# MCU103A_F280039C_Device.net
KiCad netlist of a schematic drawn in Altium Designer
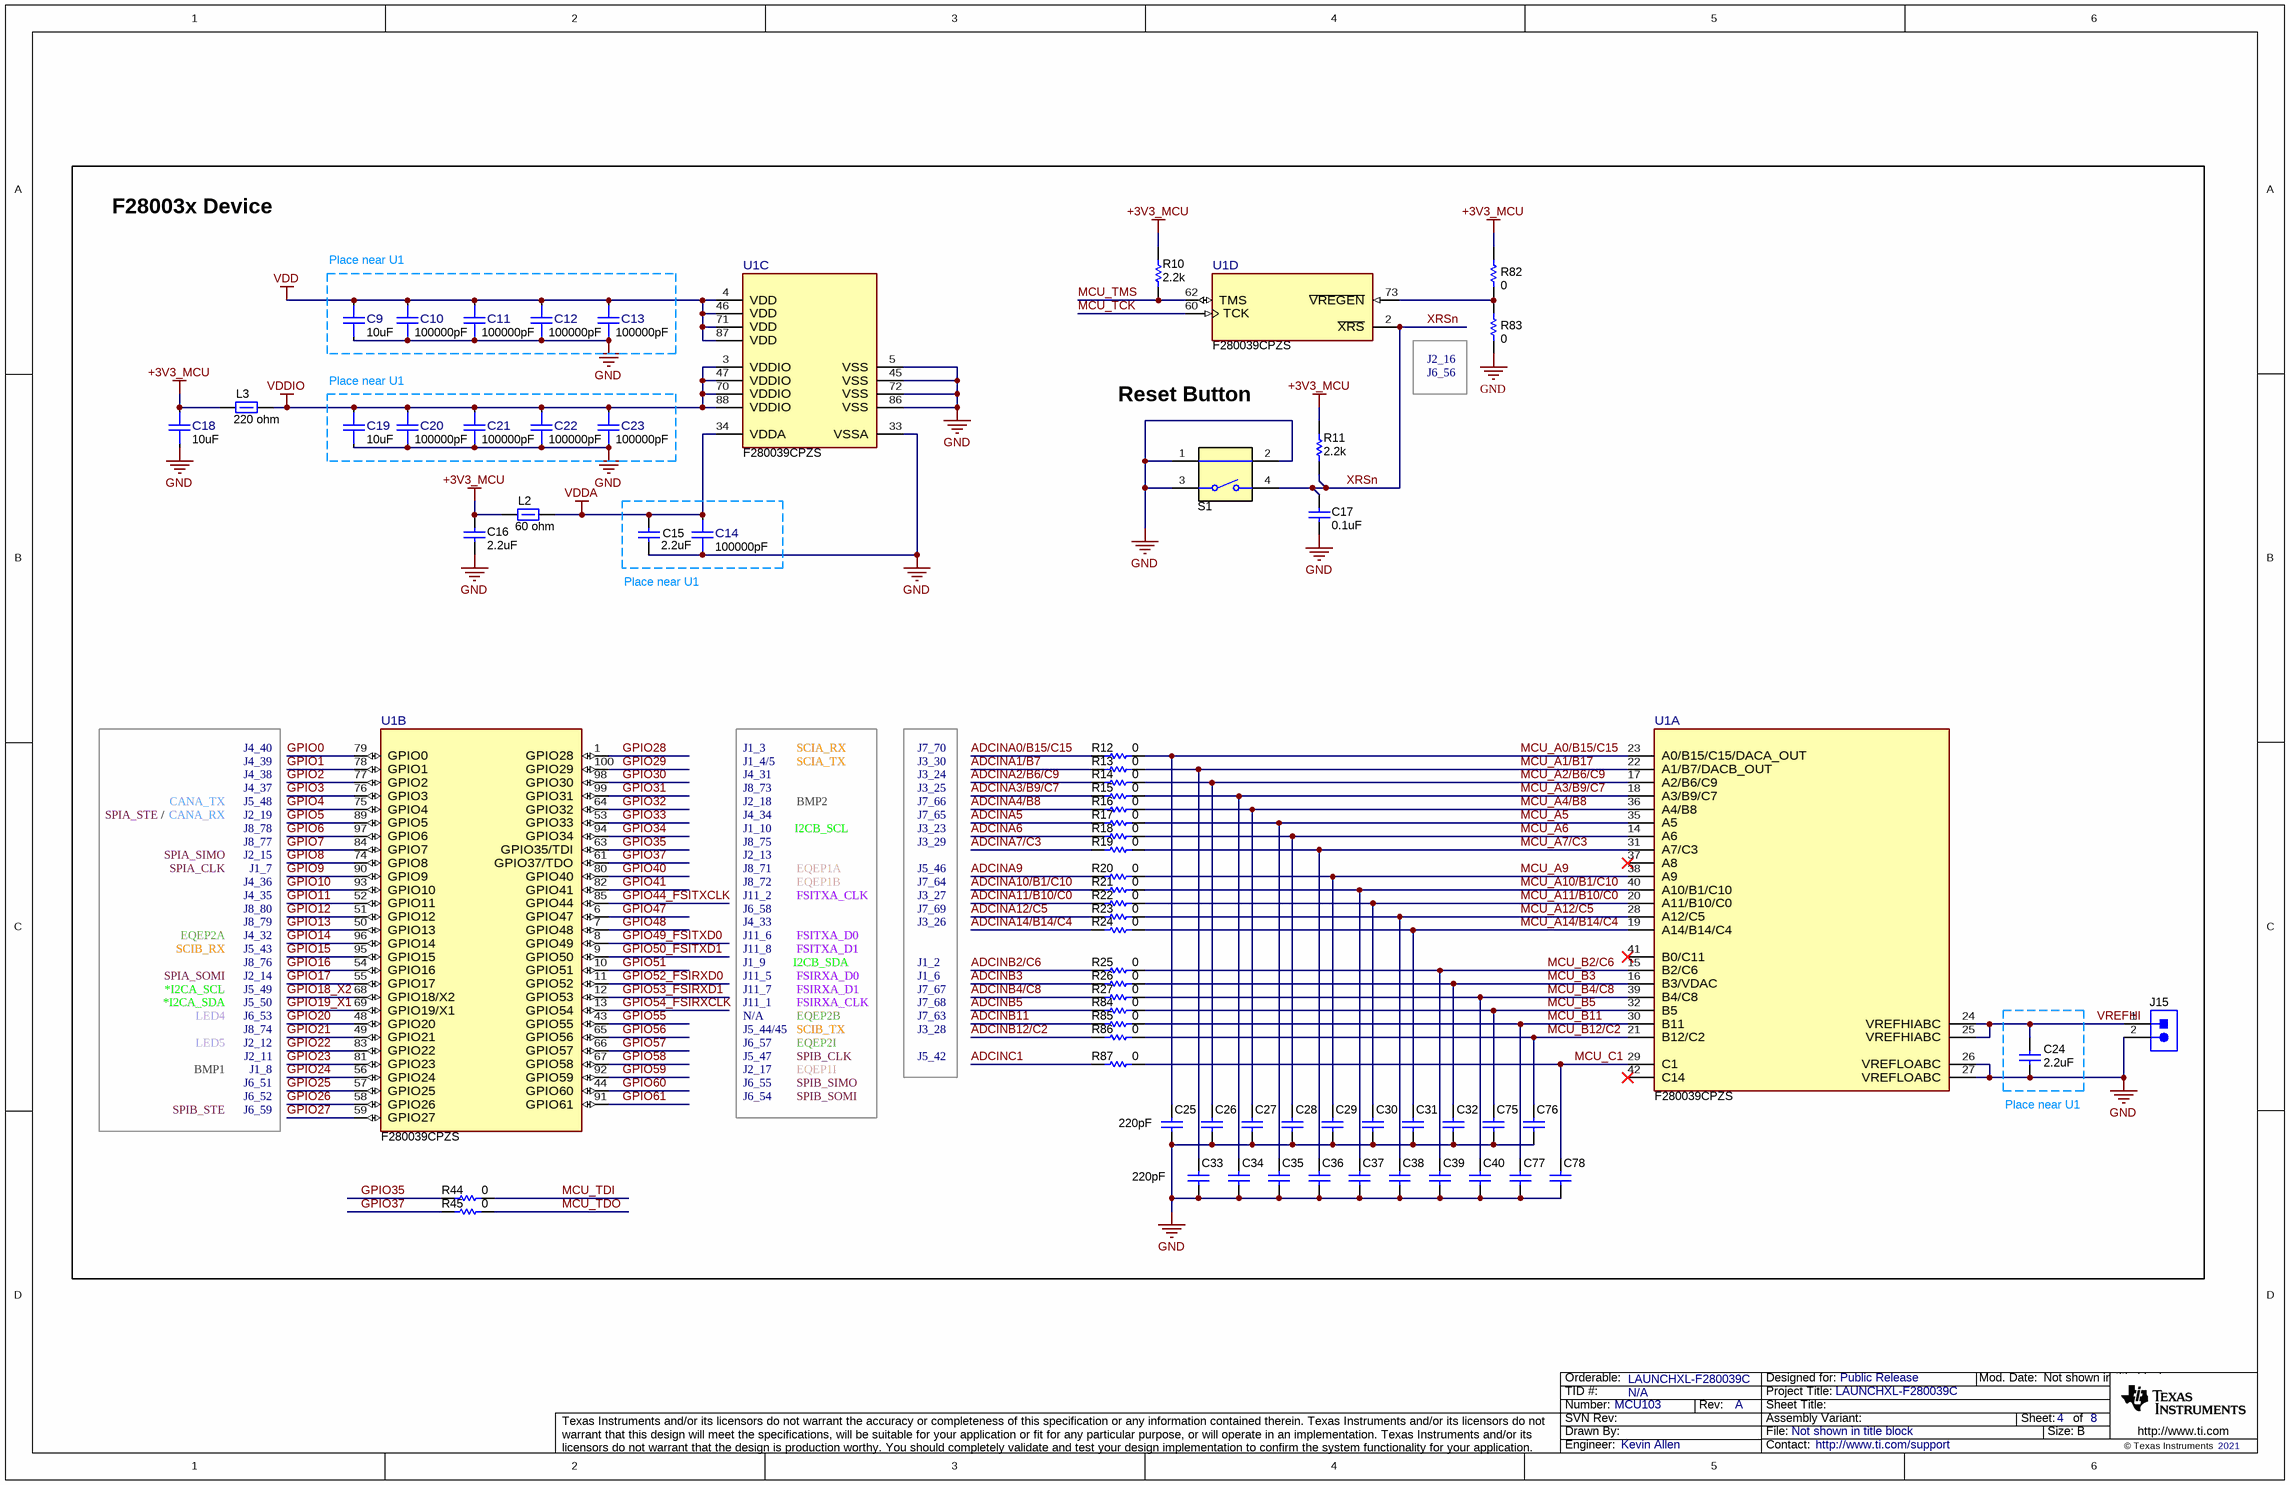
[diagram p0: MCU103A_F280039C_Device.SchDoc]

(export (version "E")
  (design (tool "Eeschema 10.0.6"))
  (components
    (comp (ref "C9")
      (value "CC0603KRX5R6BB106")
      (footprint "FP-CC0603KRX5R6BB106_0603-MFG")
      (description "Cap Ceramic 10uF 10V X5R 10% SMD 0603 85C Paper T/R")
      (fields
        (field (name "DIGIKEY PART NUMBER") "311-1782-1-ND")
        (field (name "MANUFACTURER") "YAGEO")
        (field (name "VALUEDISPLAYED") "10uF")
      )
      (libsource (lib "Altium Vault - TI") (part "SYM-CC0603KRX5R6BB106"))
    )
    (comp (ref "C10")
      (value "885012205018")
      (footprint "FP-885012205018_0402-MFG")
      (description "0.1µF ±10% 10V Ceramic Capacitor X7R 0402 (1005 Metric)")
      (fields
        (field (name "MANUFACTURER") "Wurth Electronics")
        (field (name "MOUSER PART NUMBER") "710-885012205018")
        (field (name "VALUEDISPLAYED") "100000pF")
      )
      (libsource (lib "Altium Vault - TI") (part "SYM-885012205018"))
    )
    (comp (ref "C11")
      (value "885012205018")
      (footprint "FP-885012205018_0402-MFG")
      (description "0.1µF ±10% 10V Ceramic Capacitor X7R 0402 (1005 Metric)")
      (fields
        (field (name "MANUFACTURER") "Wurth Electronics")
        (field (name "MOUSER PART NUMBER") "710-885012205018")
        (field (name "VALUEDISPLAYED") "100000pF")
      )
      (libsource (lib "Altium Vault - TI") (part "SYM-885012205018"))
    )
    (comp (ref "C12")
      (value "885012205018")
      (footprint "FP-885012205018_0402-MFG")
      (description "0.1µF ±10% 10V Ceramic Capacitor X7R 0402 (1005 Metric)")
      (fields
        (field (name "MANUFACTURER") "Wurth Electronics")
        (field (name "MOUSER PART NUMBER") "710-885012205018")
        (field (name "VALUEDISPLAYED") "100000pF")
      )
      (libsource (lib "Altium Vault - TI") (part "SYM-885012205018"))
    )
    (comp (ref "C13")
      (value "885012205018")
      (footprint "FP-885012205018_0402-MFG")
      (description "0.1µF ±10% 10V Ceramic Capacitor X7R 0402 (1005 Metric)")
      (fields
        (field (name "MANUFACTURER") "Wurth Electronics")
        (field (name "MOUSER PART NUMBER") "710-885012205018")
        (field (name "VALUEDISPLAYED") "100000pF")
      )
      (libsource (lib "Altium Vault - TI") (part "SYM-885012205018"))
    )
    (comp (ref "C14")
      (value "885012205018")
      (footprint "FP-885012205018_0402-MFG")
      (description "0.1µF ±10% 10V Ceramic Capacitor X7R 0402 (1005 Metric)")
      (fields
        (field (name "MANUFACTURER") "Wurth Electronics")
        (field (name "MOUSER PART NUMBER") "710-885012205018")
        (field (name "VALUEDISPLAYED") "100000pF")
      )
      (libsource (lib "Altium Vault - TI") (part "SYM-885012205018"))
    )
    (comp (ref "C15")
      (value "GRM188R61A225KE34D")
      (footprint "0603")
      (description "CAP, CERM, 2.2 uF, 10 V, +/- 10%, X5R, 0603")
      (fields
        (field (name "VALUEDISPLAYED") "2.2uF")
        (field (name "MANUFACTURER") "MuRata")
        (field (name "PUBLISHER") "Texas Instruments")
      )
      (libsource (lib "Altium Vault - TI") (part "Capacitor"))
    )
    (comp (ref "C16")
      (value "GRM188R61A225KE34D")
      (footprint "0603")
      (description "CAP, CERM, 2.2 uF, 10 V, +/- 10%, X5R, 0603")
      (fields
        (field (name "VALUEDISPLAYED") "2.2uF")
        (field (name "MANUFACTURER") "MuRata")
        (field (name "PUBLISHER") "Texas Instruments")
      )
      (libsource (lib "Altium Vault - TI") (part "Capacitor"))
    )
    (comp (ref "C17")
      (value "GRM155R71A104KA01D")
      (footprint "0402")
      (description "CAP, CERM, 0.1 uF, 10 V, +/- 10%, X7R, 0402")
      (fields
        (field (name "VALUEDISPLAYED") "0.1uF")
        (field (name "MANUFACTURER") "MuRata")
        (field (name "PUBLISHER") "Texas Instruments")
      )
      (libsource (lib "Altium Vault - TI") (part "Capacitor"))
    )
    (comp (ref "C18")
      (value "CC0603KRX5R6BB106")
      (footprint "FP-CC0603KRX5R6BB106_0603-MFG")
      (description "Cap Ceramic 10uF 10V X5R 10% SMD 0603 85C Paper T/R")
      (fields
        (field (name "DIGIKEY PART NUMBER") "311-1782-1-ND")
        (field (name "MANUFACTURER") "YAGEO")
        (field (name "VALUEDISPLAYED") "10uF")
      )
      (libsource (lib "Altium Vault - TI") (part "SYM-CC0603KRX5R6BB106"))
    )
    (comp (ref "C19")
      (value "CC0603KRX5R6BB106")
      (footprint "FP-CC0603KRX5R6BB106_0603-MFG")
      (description "Cap Ceramic 10uF 10V X5R 10% SMD 0603 85C Paper T/R")
      (fields
        (field (name "DIGIKEY PART NUMBER") "311-1782-1-ND")
        (field (name "MANUFACTURER") "YAGEO")
        (field (name "VALUEDISPLAYED") "10uF")
      )
      (libsource (lib "Altium Vault - TI") (part "SYM-CC0603KRX5R6BB106"))
    )
    (comp (ref "C20")
      (value "885012205018")
      (footprint "FP-885012205018_0402-MFG")
      (description "0.1µF ±10% 10V Ceramic Capacitor X7R 0402 (1005 Metric)")
      (fields
        (field (name "MANUFACTURER") "Wurth Electronics")
        (field (name "MOUSER PART NUMBER") "710-885012205018")
        (field (name "VALUEDISPLAYED") "100000pF")
      )
      (libsource (lib "Altium Vault - TI") (part "SYM-885012205018"))
    )
    (comp (ref "C21")
      (value "885012205018")
      (footprint "FP-885012205018_0402-MFG")
      (description "0.1µF ±10% 10V Ceramic Capacitor X7R 0402 (1005 Metric)")
      (fields
        (field (name "MANUFACTURER") "Wurth Electronics")
        (field (name "MOUSER PART NUMBER") "710-885012205018")
        (field (name "VALUEDISPLAYED") "100000pF")
      )
      (libsource (lib "Altium Vault - TI") (part "SYM-885012205018"))
    )
    (comp (ref "C22")
      (value "885012205018")
      (footprint "FP-885012205018_0402-MFG")
      (description "0.1µF ±10% 10V Ceramic Capacitor X7R 0402 (1005 Metric)")
      (fields
        (field (name "MANUFACTURER") "Wurth Electronics")
        (field (name "MOUSER PART NUMBER") "710-885012205018")
        (field (name "VALUEDISPLAYED") "100000pF")
      )
      (libsource (lib "Altium Vault - TI") (part "SYM-885012205018"))
    )
    (comp (ref "C23")
      (value "885012205018")
      (footprint "FP-885012205018_0402-MFG")
      (description "0.1µF ±10% 10V Ceramic Capacitor X7R 0402 (1005 Metric)")
      (fields
        (field (name "MANUFACTURER") "Wurth Electronics")
        (field (name "MOUSER PART NUMBER") "710-885012205018")
        (field (name "VALUEDISPLAYED") "100000pF")
      )
      (libsource (lib "Altium Vault - TI") (part "SYM-885012205018"))
    )
    (comp (ref "C24")
      (value "GRM188R61A225KE34D")
      (footprint "0603")
      (description "CAP, CERM, 2.2 uF, 10 V, +/- 10%, X5R, 0603")
      (fields
        (field (name "MANUFACTURER") "MuRata")
        (field (name "VALUEDISPLAYED") "2.2uF")
        (field (name "PUBLISHER") "Texas Instruments")
      )
      (libsource (lib "Altium Vault - TI") (part "Capacitor"))
    )
    (comp (ref "C25")
      (value "885012005063")
      (footprint "0402")
      (description "CAP, CERM, 220 pF, 50 V, +/- 5%, C0G/NP0, 0402")
      (fields
        (field (name "MANUFACTURER") "Wurth Elektronik")
        (field (name "VALUEDISPLAYED") "220pF")
        (field (name "PUBLISHER") "Texas Instruments")
      )
      (libsource (lib "Altium Vault - TI") (part "Capacitor"))
    )
    (comp (ref "C26")
      (value "885012005063")
      (footprint "0402")
      (description "CAP, CERM, 220 pF, 50 V, +/- 5%, C0G/NP0, 0402")
      (fields (field (name "MANUFACTURER") "Wurth Elektronik") (field (name "PUBLISHER") "Texas Instruments"))
      (libsource (lib "Altium Vault - TI") (part "Capacitor"))
    )
    (comp (ref "C27")
      (value "885012005063")
      (footprint "0402")
      (description "CAP, CERM, 220 pF, 50 V, +/- 5%, C0G/NP0, 0402")
      (fields (field (name "MANUFACTURER") "Wurth Elektronik") (field (name "PUBLISHER") "Texas Instruments"))
      (libsource (lib "Altium Vault - TI") (part "Capacitor"))
    )
    (comp (ref "C28")
      (value "885012005063")
      (footprint "0402")
      (description "CAP, CERM, 220 pF, 50 V, +/- 5%, C0G/NP0, 0402")
      (fields (field (name "MANUFACTURER") "Wurth Elektronik") (field (name "PUBLISHER") "Texas Instruments"))
      (libsource (lib "Altium Vault - TI") (part "Capacitor"))
    )
    (comp (ref "C29")
      (value "885012005063")
      (footprint "0402")
      (description "CAP, CERM, 220 pF, 50 V, +/- 5%, C0G/NP0, 0402")
      (fields (field (name "MANUFACTURER") "Wurth Elektronik") (field (name "PUBLISHER") "Texas Instruments"))
      (libsource (lib "Altium Vault - TI") (part "Capacitor"))
    )
    (comp (ref "C30")
      (value "885012005063")
      (footprint "0402")
      (description "CAP, CERM, 220 pF, 50 V, +/- 5%, C0G/NP0, 0402")
      (fields (field (name "MANUFACTURER") "Wurth Elektronik") (field (name "PUBLISHER") "Texas Instruments"))
      (libsource (lib "Altium Vault - TI") (part "Capacitor"))
    )
    (comp (ref "C31")
      (value "885012005063")
      (footprint "0402")
      (description "CAP, CERM, 220 pF, 50 V, +/- 5%, C0G/NP0, 0402")
      (fields (field (name "MANUFACTURER") "Wurth Elektronik") (field (name "PUBLISHER") "Texas Instruments"))
      (libsource (lib "Altium Vault - TI") (part "Capacitor"))
    )
    (comp (ref "C32")
      (value "885012005063")
      (footprint "0402")
      (description "CAP, CERM, 220 pF, 50 V, +/- 5%, C0G/NP0, 0402")
      (fields (field (name "MANUFACTURER") "Wurth Elektronik") (field (name "PUBLISHER") "Texas Instruments"))
      (libsource (lib "Altium Vault - TI") (part "Capacitor"))
    )
    (comp (ref "C33")
      (value "885012005063")
      (footprint "0402")
      (description "CAP, CERM, 220 pF, 50 V, +/- 5%, C0G/NP0, 0402")
      (fields
        (field (name "MANUFACTURER") "Wurth Elektronik")
        (field (name "VALUEDISPLAYED") "220pF")
        (field (name "PUBLISHER") "Texas Instruments")
      )
      (libsource (lib "Altium Vault - TI") (part "Capacitor"))
    )
    (comp (ref "C34")
      (value "885012005063")
      (footprint "0402")
      (description "CAP, CERM, 220 pF, 50 V, +/- 5%, C0G/NP0, 0402")
      (fields (field (name "MANUFACTURER") "Wurth Elektronik") (field (name "PUBLISHER") "Texas Instruments"))
      (libsource (lib "Altium Vault - TI") (part "Capacitor"))
    )
    (comp (ref "C35")
      (value "885012005063")
      (footprint "0402")
      (description "CAP, CERM, 220 pF, 50 V, +/- 5%, C0G/NP0, 0402")
      (fields (field (name "MANUFACTURER") "Wurth Elektronik") (field (name "PUBLISHER") "Texas Instruments"))
      (libsource (lib "Altium Vault - TI") (part "Capacitor"))
    )
    (comp (ref "C36")
      (value "885012005063")
      (footprint "0402")
      (description "CAP, CERM, 220 pF, 50 V, +/- 5%, C0G/NP0, 0402")
      (fields (field (name "MANUFACTURER") "Wurth Elektronik") (field (name "PUBLISHER") "Texas Instruments"))
      (libsource (lib "Altium Vault - TI") (part "Capacitor"))
    )
    (comp (ref "C37")
      (value "885012005063")
      (footprint "0402")
      (description "CAP, CERM, 220 pF, 50 V, +/- 5%, C0G/NP0, 0402")
      (fields (field (name "MANUFACTURER") "Wurth Elektronik") (field (name "PUBLISHER") "Texas Instruments"))
      (libsource (lib "Altium Vault - TI") (part "Capacitor"))
    )
    (comp (ref "C38")
      (value "885012005063")
      (footprint "0402")
      (description "CAP, CERM, 220 pF, 50 V, +/- 5%, C0G/NP0, 0402")
      (fields (field (name "MANUFACTURER") "Wurth Elektronik") (field (name "PUBLISHER") "Texas Instruments"))
      (libsource (lib "Altium Vault - TI") (part "Capacitor"))
    )
    (comp (ref "C39")
      (value "885012005063")
      (footprint "0402")
      (description "CAP, CERM, 220 pF, 50 V, +/- 5%, C0G/NP0, 0402")
      (fields (field (name "MANUFACTURER") "Wurth Elektronik") (field (name "PUBLISHER") "Texas Instruments"))
      (libsource (lib "Altium Vault - TI") (part "Capacitor"))
    )
    (comp (ref "C40")
      (value "885012005063")
      (footprint "0402")
      (description "CAP, CERM, 220 pF, 50 V, +/- 5%, C0G/NP0, 0402")
      (fields (field (name "MANUFACTURER") "Wurth Elektronik") (field (name "PUBLISHER") "Texas Instruments"))
      (libsource (lib "Altium Vault - TI") (part "Capacitor"))
    )
    (comp (ref "C75")
      (value "885012005063")
      (footprint "0402")
      (description "CAP, CERM, 220 pF, 50 V, +/- 5%, C0G/NP0, 0402")
      (fields (field (name "MANUFACTURER") "Wurth Elektronik") (field (name "PUBLISHER") "Texas Instruments"))
      (libsource (lib "Altium Vault - TI") (part "Capacitor"))
    )
    (comp (ref "C76")
      (value "885012005063")
      (footprint "0402")
      (description "CAP, CERM, 220 pF, 50 V, +/- 5%, C0G/NP0, 0402")
      (fields (field (name "MANUFACTURER") "Wurth Elektronik") (field (name "PUBLISHER") "Texas Instruments"))
      (libsource (lib "Altium Vault - TI") (part "Capacitor"))
    )
    (comp (ref "C77")
      (value "885012005063")
      (footprint "0402")
      (description "CAP, CERM, 220 pF, 50 V, +/- 5%, C0G/NP0, 0402")
      (fields (field (name "MANUFACTURER") "Wurth Elektronik") (field (name "PUBLISHER") "Texas Instruments"))
      (libsource (lib "Altium Vault - TI") (part "Capacitor"))
    )
    (comp (ref "C78")
      (value "885012005063")
      (footprint "0402")
      (description "CAP, CERM, 220 pF, 50 V, +/- 5%, C0G/NP0, 0402")
      (fields (field (name "MANUFACTURER") "Wurth Elektronik") (field (name "PUBLISHER") "Texas Instruments"))
      (libsource (lib "Altium Vault - TI") (part "Capacitor"))
    )
    (comp (ref "J15")
      (value "61300211121")
      (footprint "WURTH_61300211121")
      (description "Header, 2.54 mm, 2x1, Gold, TH")
      (fields (field (name "MANUFACTURER") "Wurth Elektronik") (field (name "PUBLISHER") "Texas Instruments"))
      (libsource (lib "Altium Vault - TI") (part "Header_2x1"))
    )
    (comp (ref "L2")
      (value "60 ohm")
      (footprint "0805_HV")
      (description "Ferrite Bead, 60 ohm @ 100 MHz, 3 A, 0805")
      (fields
        (field (name "MANUFACTURER") "Wurth Elektronik")
        (field (name "PARTNUMBER") "742792063")
        (field (name "PUBLISHER") "Texas Instruments")
      )
      (libsource (lib "Altium Vault - TI") (part "Ferrite_Bead"))
    )
    (comp (ref "L3")
      (value "742792022")
      (footprint "0805_HV")
      (description "Ferrite Bead, 220 ohm @ 100 MHz, 2 A, 0805")
      (fields
        (field (name "MANUFACTURER") "Wurth Elektronik")
        (field (name "VALUEDISPLAYED") "220 ohm")
        (field (name "PUBLISHER") "Texas Instruments")
      )
      (libsource (lib "Altium Vault - TI") (part "Ferrite_Bead"))
    )
    (comp (ref "R10")
      (value "CRCW04022K20JNED")
      (footprint "0402")
      (description "RES, 2.2 k, 5%, 0.063 W, AEC-Q200 Grade 0, 0402")
      (fields (field (name "VALUEDISPLAYED") "2.2k") (field (name "MANUFACTURER") "Vishay-Dale"))
      (libsource (lib "Altium Vault - TI") (part "Resistor"))
    )
    (comp (ref "R11")
      (value "CRCW04022K20JNED")
      (footprint "0402")
      (description "RES, 2.2 k, 5%, 0.063 W, AEC-Q200 Grade 0, 0402")
      (fields (field (name "VALUEDISPLAYED") "2.2k") (field (name "MANUFACTURER") "Vishay-Dale"))
      (libsource (lib "Altium Vault - TI") (part "Resistor"))
    )
    (comp (ref "R12")
      (value "RC0402JR-070RL")
      (footprint "0402")
      (description "RES, 0, 5%, 0.063 W, 0402")
      (fields
        (field (name "MANUFACTURER") "Yageo America")
        (field (name "VALUEDISPLAYED") "0")
        (field (name "PUBLISHER") "Texas Instruments")
      )
      (libsource (lib "Altium Vault - TI") (part "Resistor"))
    )
    (comp (ref "R13")
      (value "RC0402JR-070RL")
      (footprint "0402")
      (description "RES, 0, 5%, 0.063 W, 0402")
      (fields
        (field (name "MANUFACTURER") "Yageo America")
        (field (name "VALUEDISPLAYED") "0")
        (field (name "PUBLISHER") "Texas Instruments")
      )
      (libsource (lib "Altium Vault - TI") (part "Resistor"))
    )
    (comp (ref "R14")
      (value "RC0402JR-070RL")
      (footprint "0402")
      (description "RES, 0, 5%, 0.063 W, 0402")
      (fields
        (field (name "MANUFACTURER") "Yageo America")
        (field (name "VALUEDISPLAYED") "0")
        (field (name "PUBLISHER") "Texas Instruments")
      )
      (libsource (lib "Altium Vault - TI") (part "Resistor"))
    )
    (comp (ref "R15")
      (value "RC0402JR-070RL")
      (footprint "0402")
      (description "RES, 0, 5%, 0.063 W, 0402")
      (fields
        (field (name "MANUFACTURER") "Yageo America")
        (field (name "VALUEDISPLAYED") "0")
        (field (name "PUBLISHER") "Texas Instruments")
      )
      (libsource (lib "Altium Vault - TI") (part "Resistor"))
    )
    (comp (ref "R16")
      (value "RC0402JR-070RL")
      (footprint "0402")
      (description "RES, 0, 5%, 0.063 W, 0402")
      (fields
        (field (name "MANUFACTURER") "Yageo America")
        (field (name "VALUEDISPLAYED") "0")
        (field (name "PUBLISHER") "Texas Instruments")
      )
      (libsource (lib "Altium Vault - TI") (part "Resistor"))
    )
    (comp (ref "R17")
      (value "RC0402JR-070RL")
      (footprint "0402")
      (description "RES, 0, 5%, 0.063 W, 0402")
      (fields
        (field (name "MANUFACTURER") "Yageo America")
        (field (name "VALUEDISPLAYED") "0")
        (field (name "PUBLISHER") "Texas Instruments")
      )
      (libsource (lib "Altium Vault - TI") (part "Resistor"))
    )
    (comp (ref "R18")
      (value "RC0402JR-070RL")
      (footprint "0402")
      (description "RES, 0, 5%, 0.063 W, 0402")
      (fields
        (field (name "MANUFACTURER") "Yageo America")
        (field (name "VALUEDISPLAYED") "0")
        (field (name "PUBLISHER") "Texas Instruments")
      )
      (libsource (lib "Altium Vault - TI") (part "Resistor"))
    )
    (comp (ref "R19")
      (value "RC0402JR-070RL")
      (footprint "0402")
      (description "RES, 0, 5%, 0.063 W, 0402")
      (fields
        (field (name "MANUFACTURER") "Yageo America")
        (field (name "VALUEDISPLAYED") "0")
        (field (name "PUBLISHER") "Texas Instruments")
      )
      (libsource (lib "Altium Vault - TI") (part "Resistor"))
    )
    (comp (ref "R20")
      (value "RC0402JR-070RL")
      (footprint "0402")
      (description "RES, 0, 5%, 0.063 W, 0402")
      (fields
        (field (name "MANUFACTURER") "Yageo America")
        (field (name "VALUEDISPLAYED") "0")
        (field (name "PUBLISHER") "Texas Instruments")
      )
      (libsource (lib "Altium Vault - TI") (part "Resistor"))
    )
    (comp (ref "R21")
      (value "RC0402JR-070RL")
      (footprint "0402")
      (description "RES, 0, 5%, 0.063 W, 0402")
      (fields
        (field (name "MANUFACTURER") "Yageo America")
        (field (name "VALUEDISPLAYED") "0")
        (field (name "PUBLISHER") "Texas Instruments")
      )
      (libsource (lib "Altium Vault - TI") (part "Resistor"))
    )
    (comp (ref "R22")
      (value "RC0402JR-070RL")
      (footprint "0402")
      (description "RES, 0, 5%, 0.063 W, 0402")
      (fields
        (field (name "MANUFACTURER") "Yageo America")
        (field (name "VALUEDISPLAYED") "0")
        (field (name "PUBLISHER") "Texas Instruments")
      )
      (libsource (lib "Altium Vault - TI") (part "Resistor"))
    )
    (comp (ref "R23")
      (value "RC0402JR-070RL")
      (footprint "0402")
      (description "RES, 0, 5%, 0.063 W, 0402")
      (fields
        (field (name "MANUFACTURER") "Yageo America")
        (field (name "VALUEDISPLAYED") "0")
        (field (name "PUBLISHER") "Texas Instruments")
      )
      (libsource (lib "Altium Vault - TI") (part "Resistor"))
    )
    (comp (ref "R24")
      (value "RC0402JR-070RL")
      (footprint "0402")
      (description "RES, 0, 5%, 0.063 W, 0402")
      (fields
        (field (name "MANUFACTURER") "Yageo America")
        (field (name "VALUEDISPLAYED") "0")
        (field (name "PUBLISHER") "Texas Instruments")
      )
      (libsource (lib "Altium Vault - TI") (part "Resistor"))
    )
    (comp (ref "R25")
      (value "RC0402JR-070RL")
      (footprint "0402")
      (description "RES, 0, 5%, 0.063 W, 0402")
      (fields
        (field (name "MANUFACTURER") "Yageo America")
        (field (name "VALUEDISPLAYED") "0")
        (field (name "PUBLISHER") "Texas Instruments")
      )
      (libsource (lib "Altium Vault - TI") (part "Resistor"))
    )
    (comp (ref "R26")
      (value "RC0402JR-070RL")
      (footprint "0402")
      (description "RES, 0, 5%, 0.063 W, 0402")
      (fields
        (field (name "MANUFACTURER") "Yageo America")
        (field (name "VALUEDISPLAYED") "0")
        (field (name "PUBLISHER") "Texas Instruments")
      )
      (libsource (lib "Altium Vault - TI") (part "Resistor"))
    )
    (comp (ref "R27")
      (value "RC0402JR-070RL")
      (footprint "0402")
      (description "RES, 0, 5%, 0.063 W, 0402")
      (fields
        (field (name "MANUFACTURER") "Yageo America")
        (field (name "VALUEDISPLAYED") "0")
        (field (name "PUBLISHER") "Texas Instruments")
      )
      (libsource (lib "Altium Vault - TI") (part "Resistor"))
    )
    (comp (ref "R44")
      (value "RC0402JR-070RL")
      (footprint "0402")
      (description "RES, 0, 5%, 0.063 W, 0402")
      (fields
        (field (name "MANUFACTURER") "Yageo America")
        (field (name "VALUEDISPLAYED") "0")
        (field (name "PUBLISHER") "Texas Instruments")
      )
      (libsource (lib "Altium Vault - TI") (part "Resistor"))
    )
    (comp (ref "R45")
      (value "RC0402JR-070RL")
      (footprint "0402")
      (description "RES, 0, 5%, 0.063 W, 0402")
      (fields
        (field (name "MANUFACTURER") "Yageo America")
        (field (name "VALUEDISPLAYED") "0")
        (field (name "PUBLISHER") "Texas Instruments")
      )
      (libsource (lib "Altium Vault - TI") (part "Resistor"))
    )
    (comp (ref "R82")
      (value "CRCW06030000Z0EA")
      (footprint "0603")
      (description "RES, 0, 5%, 0.1 W, AEC-Q200 Grade 0, 0603")
      (fields (field (name "VALUEDISPLAYED") "0") (field (name "MANUFACTURER") "Vishay-Dale"))
      (libsource (lib "Altium Vault - TI") (part "Resistor"))
    )
    (comp (ref "R83")
      (value "CRCW06030000Z0EA")
      (footprint "0603")
      (description "RES, 0, 5%, 0.1 W, AEC-Q200 Grade 0, 0603")
      (fields (field (name "VALUEDISPLAYED") "0") (field (name "MANUFACTURER") "Vishay-Dale"))
      (libsource (lib "Altium Vault - TI") (part "Resistor"))
    )
    (comp (ref "R84")
      (value "RC0402JR-070RL")
      (footprint "0402")
      (description "RES, 0, 5%, 0.063 W, 0402")
      (fields
        (field (name "MANUFACTURER") "Yageo America")
        (field (name "VALUEDISPLAYED") "0")
        (field (name "PUBLISHER") "Texas Instruments")
      )
      (libsource (lib "Altium Vault - TI") (part "Resistor"))
    )
    (comp (ref "R85")
      (value "RC0402JR-070RL")
      (footprint "0402")
      (description "RES, 0, 5%, 0.063 W, 0402")
      (fields
        (field (name "MANUFACTURER") "Yageo America")
        (field (name "VALUEDISPLAYED") "0")
        (field (name "PUBLISHER") "Texas Instruments")
      )
      (libsource (lib "Altium Vault - TI") (part "Resistor"))
    )
    (comp (ref "R86")
      (value "RC0402JR-070RL")
      (footprint "0402")
      (description "RES, 0, 5%, 0.063 W, 0402")
      (fields
        (field (name "MANUFACTURER") "Yageo America")
        (field (name "VALUEDISPLAYED") "0")
        (field (name "PUBLISHER") "Texas Instruments")
      )
      (libsource (lib "Altium Vault - TI") (part "Resistor"))
    )
    (comp (ref "R87")
      (value "RC0402JR-070RL")
      (footprint "0402")
      (description "RES, 0, 5%, 0.063 W, 0402")
      (fields
        (field (name "MANUFACTURER") "Yageo America")
        (field (name "VALUEDISPLAYED") "0")
        (field (name "PUBLISHER") "Texas Instruments")
      )
      (libsource (lib "Altium Vault - TI") (part "Resistor"))
    )
    (comp (ref "S1")
      (value "1188E-1K2-V-TR")
      (footprint "SW_1188E")
      (description "Switch, SPST, 0.05 A, 12 VDC, SMD")
      (fields (field (name "MANUFACTURER") "Diptronics") (field (name "PUBLISHER") "Texas Instruments"))
      (libsource (lib "Altium Vault - TI") (part "SW_1188E"))
    )
    (comp (ref "U1")
      (value "F280039CPZS")
      (footprint "PZ0100A-MFG")
      (description "Real-Time Microcontroller 32bit, 120MHz, 384KBytes Flash, 69KBytes RAM, PQFP100")
      (fields (field (name "PARTNUMBER") "F280039CPZS") (field (name "MANUFACTURER") "Texas Instruments"))
      (libsource (lib "Altium Vault - TI") (part "SYM-F280039CPZS"))
    )
  )
  (nets
    (net (code "1") (name "+3V3_MCU") (class "Default")
      (node (ref "C16") (pin "1") (pinfunction "1_1") (pintype "passive"))
      (node (ref "C18") (pin "2") (pinfunction "2_2") (pintype "passive"))
      (node (ref "L2") (pin "1") (pinfunction "1_1") (pintype "passive"))
      (node (ref "L3") (pin "1") (pinfunction "1_1") (pintype "passive"))
      (node (ref "R10") (pin "2") (pinfunction "2_2") (pintype "passive"))
      (node (ref "R11") (pin "2") (pinfunction "2_2") (pintype "passive"))
      (node (ref "R82") (pin "1") (pinfunction "1_1") (pintype "passive"))
    )
    (net (code "2") (name "/ADCINA0{slash}B15{slash}C15") (class "Default")
      (node (ref "R12") (pin "1") (pinfunction "1_1") (pintype "passive"))
    )
    (net (code "3") (name "/ADCINA1{slash}B7") (class "Default")
      (node (ref "R13") (pin "1") (pinfunction "1_1") (pintype "passive"))
    )
    (net (code "4") (name "/ADCINA2{slash}B6{slash}C9") (class "Default")
      (node (ref "R14") (pin "1") (pinfunction "1_1") (pintype "passive"))
    )
    (net (code "5") (name "/ADCINA3{slash}B9{slash}C7") (class "Default")
      (node (ref "R15") (pin "1") (pinfunction "1_1") (pintype "passive"))
    )
    (net (code "6") (name "/ADCINA4{slash}B8") (class "Default")
      (node (ref "R16") (pin "1") (pinfunction "1_1") (pintype "passive"))
    )
    (net (code "7") (name "/ADCINA5") (class "Default")
      (node (ref "R17") (pin "1") (pinfunction "1_1") (pintype "passive"))
    )
    (net (code "8") (name "/ADCINA6") (class "Default")
      (node (ref "R18") (pin "1") (pinfunction "1_1") (pintype "passive"))
    )
    (net (code "9") (name "/ADCINA7{slash}C3") (class "Default")
      (node (ref "R19") (pin "1") (pinfunction "1_1") (pintype "passive"))
    )
    (net (code "10") (name "/ADCINA9") (class "Default")
      (node (ref "R20") (pin "1") (pinfunction "1_1") (pintype "passive"))
    )
    (net (code "11") (name "/ADCINA10{slash}B1{slash}C10") (class "Default")
      (node (ref "R21") (pin "1") (pinfunction "1_1") (pintype "passive"))
    )
    (net (code "12") (name "/ADCINA11{slash}B10{slash}C0") (class "Default")
      (node (ref "R22") (pin "1") (pinfunction "1_1") (pintype "passive"))
    )
    (net (code "13") (name "/ADCINA12{slash}C5") (class "Default")
      (node (ref "R23") (pin "1") (pinfunction "1_1") (pintype "passive"))
    )
    (net (code "14") (name "/ADCINA14{slash}B14{slash}C4") (class "Default")
      (node (ref "R24") (pin "1") (pinfunction "1_1") (pintype "passive"))
    )
    (net (code "15") (name "/ADCINB2{slash}C6") (class "Default")
      (node (ref "R25") (pin "1") (pinfunction "1_1") (pintype "passive"))
    )
    (net (code "16") (name "/ADCINB3") (class "Default")
      (node (ref "R26") (pin "1") (pinfunction "1_1") (pintype "passive"))
    )
    (net (code "17") (name "/ADCINB4{slash}C8") (class "Default")
      (node (ref "R27") (pin "1") (pinfunction "1_1") (pintype "passive"))
    )
    (net (code "18") (name "/ADCINB5") (class "Default")
      (node (ref "R84") (pin "1") (pinfunction "1_1") (pintype "passive"))
    )
    (net (code "19") (name "/ADCINB11") (class "Default")
      (node (ref "R85") (pin "1") (pinfunction "1_1") (pintype "passive"))
    )
    (net (code "20") (name "/ADCINB12{slash}C2") (class "Default")
      (node (ref "R86") (pin "1") (pinfunction "1_1") (pintype "passive"))
    )
    (net (code "21") (name "/ADCINC1") (class "Default")
      (node (ref "R87") (pin "1") (pinfunction "1_1") (pintype "passive"))
    )
    (net (code "22") (name "/GPIO0") (class "Default")
      (node (ref "U1") (pin "79") (pinfunction "GPIO0_79") (pintype "bidirectional"))
    )
    (net (code "23") (name "/GPIO1") (class "Default")
      (node (ref "U1") (pin "78") (pinfunction "GPIO1_78") (pintype "bidirectional"))
    )
    (net (code "24") (name "/GPIO2") (class "Default")
      (node (ref "U1") (pin "77") (pinfunction "GPIO2_77") (pintype "bidirectional"))
    )
    (net (code "25") (name "/GPIO3") (class "Default")
      (node (ref "U1") (pin "76") (pinfunction "GPIO3_76") (pintype "bidirectional"))
    )
    (net (code "26") (name "/GPIO4") (class "Default")
      (node (ref "U1") (pin "75") (pinfunction "GPIO4_75") (pintype "bidirectional"))
    )
    (net (code "27") (name "/GPIO5") (class "Default")
      (node (ref "U1") (pin "89") (pinfunction "GPIO5_89") (pintype "bidirectional"))
    )
    (net (code "28") (name "/GPIO6") (class "Default")
      (node (ref "U1") (pin "97") (pinfunction "GPIO6_97") (pintype "bidirectional"))
    )
    (net (code "29") (name "/GPIO7") (class "Default")
      (node (ref "U1") (pin "84") (pinfunction "GPIO7_84") (pintype "bidirectional"))
    )
    (net (code "30") (name "/GPIO8") (class "Default")
      (node (ref "U1") (pin "74") (pinfunction "GPIO8_74") (pintype "bidirectional"))
    )
    (net (code "31") (name "/GPIO9") (class "Default")
      (node (ref "U1") (pin "90") (pinfunction "GPIO9_90") (pintype "bidirectional"))
    )
    (net (code "32") (name "/GPIO10") (class "Default")
      (node (ref "U1") (pin "93") (pinfunction "GPIO10_93") (pintype "bidirectional"))
    )
    (net (code "33") (name "/GPIO11") (class "Default")
      (node (ref "U1") (pin "52") (pinfunction "GPIO11_52") (pintype "bidirectional"))
    )
    (net (code "34") (name "/GPIO12") (class "Default")
      (node (ref "U1") (pin "51") (pinfunction "GPIO12_51") (pintype "bidirectional"))
    )
    (net (code "35") (name "/GPIO13") (class "Default")
      (node (ref "U1") (pin "50") (pinfunction "GPIO13_50") (pintype "bidirectional"))
    )
    (net (code "36") (name "/GPIO14") (class "Default")
      (node (ref "U1") (pin "96") (pinfunction "GPIO14_96") (pintype "bidirectional"))
    )
    (net (code "37") (name "/GPIO15") (class "Default")
      (node (ref "U1") (pin "95") (pinfunction "GPIO15_95") (pintype "bidirectional"))
    )
    (net (code "38") (name "/GPIO16") (class "Default")
      (node (ref "U1") (pin "54") (pinfunction "GPIO16_54") (pintype "bidirectional"))
    )
    (net (code "39") (name "/GPIO17") (class "Default")
      (node (ref "U1") (pin "55") (pinfunction "GPIO17_55") (pintype "bidirectional"))
    )
    (net (code "40") (name "/GPIO18_X2") (class "Default")
      (node (ref "U1") (pin "68") (pinfunction "GPIO18/X2_68") (pintype "bidirectional"))
    )
    (net (code "41") (name "/GPIO19_X1") (class "Default")
      (node (ref "U1") (pin "69") (pinfunction "GPIO19/X1_69") (pintype "bidirectional"))
    )
    (net (code "42") (name "/GPIO20") (class "Default")
      (node (ref "U1") (pin "48") (pinfunction "GPIO20_48") (pintype "bidirectional"))
    )
    (net (code "43") (name "/GPIO21") (class "Default")
      (node (ref "U1") (pin "49") (pinfunction "GPIO21_49") (pintype "bidirectional"))
    )
    (net (code "44") (name "/GPIO22") (class "Default")
      (node (ref "U1") (pin "83") (pinfunction "GPIO22_83") (pintype "bidirectional"))
    )
    (net (code "45") (name "/GPIO23") (class "Default")
      (node (ref "U1") (pin "81") (pinfunction "GPIO23_81") (pintype "bidirectional"))
    )
    (net (code "46") (name "/GPIO24") (class "Default")
      (node (ref "U1") (pin "56") (pinfunction "GPIO24_56") (pintype "bidirectional"))
    )
    (net (code "47") (name "/GPIO25") (class "Default")
      (node (ref "U1") (pin "57") (pinfunction "GPIO25_57") (pintype "bidirectional"))
    )
    (net (code "48") (name "/GPIO26") (class "Default")
      (node (ref "U1") (pin "58") (pinfunction "GPIO26_58") (pintype "bidirectional"))
    )
    (net (code "49") (name "/GPIO27") (class "Default")
      (node (ref "U1") (pin "59") (pinfunction "GPIO27_59") (pintype "bidirectional"))
    )
    (net (code "50") (name "/GPIO28") (class "Default")
      (node (ref "U1") (pin "1") (pinfunction "GPIO28_1") (pintype "bidirectional"))
    )
    (net (code "51") (name "/GPIO29") (class "Default")
      (node (ref "U1") (pin "100") (pinfunction "GPIO29_100") (pintype "bidirectional"))
    )
    (net (code "52") (name "/GPIO30") (class "Default")
      (node (ref "U1") (pin "98") (pinfunction "GPIO30_98") (pintype "bidirectional"))
    )
    (net (code "53") (name "/GPIO31") (class "Default")
      (node (ref "U1") (pin "99") (pinfunction "GPIO31_99") (pintype "bidirectional"))
    )
    (net (code "54") (name "/GPIO32") (class "Default")
      (node (ref "U1") (pin "64") (pinfunction "GPIO32_64") (pintype "bidirectional"))
    )
    (net (code "55") (name "/GPIO33") (class "Default")
      (node (ref "U1") (pin "53") (pinfunction "GPIO33_53") (pintype "bidirectional"))
    )
    (net (code "56") (name "/GPIO34") (class "Default")
      (node (ref "U1") (pin "94") (pinfunction "GPIO34_94") (pintype "bidirectional"))
    )
    (net (code "57") (name "/GPIO35") (class "Default")
      (node (ref "R44") (pin "1") (pinfunction "1_1") (pintype "passive"))
      (node (ref "U1") (pin "63") (pinfunction "GPIO35/TDI_63") (pintype "bidirectional"))
    )
    (net (code "58") (name "/GPIO37") (class "Default")
      (node (ref "R45") (pin "1") (pinfunction "1_1") (pintype "passive"))
      (node (ref "U1") (pin "61") (pinfunction "GPIO37/TDO_61") (pintype "bidirectional"))
    )
    (net (code "59") (name "/GPIO40") (class "Default")
      (node (ref "U1") (pin "80") (pinfunction "GPIO40_80") (pintype "bidirectional"))
    )
    (net (code "60") (name "/GPIO41") (class "Default")
      (node (ref "U1") (pin "82") (pinfunction "GPIO41_82") (pintype "bidirectional"))
    )
    (net (code "61") (name "/GPIO44_FSITXCLK") (class "Default")
      (node (ref "U1") (pin "85") (pinfunction "GPIO44_85") (pintype "bidirectional"))
    )
    (net (code "62") (name "/GPIO47") (class "Default")
      (node (ref "U1") (pin "6") (pinfunction "GPIO47_6") (pintype "bidirectional"))
    )
    (net (code "63") (name "/GPIO48") (class "Default")
      (node (ref "U1") (pin "7") (pinfunction "GPIO48_7") (pintype "bidirectional"))
    )
    (net (code "64") (name "/GPIO49_FSITXD0") (class "Default")
      (node (ref "U1") (pin "8") (pinfunction "GPIO49_8") (pintype "bidirectional"))
    )
    (net (code "65") (name "/GPIO50_FSITXD1") (class "Default")
      (node (ref "U1") (pin "9") (pinfunction "GPIO50_9") (pintype "bidirectional"))
    )
    (net (code "66") (name "/GPIO51") (class "Default")
      (node (ref "U1") (pin "10") (pinfunction "GPIO51_10") (pintype "bidirectional"))
    )
    (net (code "67") (name "/GPIO52_FSIRXD0") (class "Default")
      (node (ref "U1") (pin "11") (pinfunction "GPIO52_11") (pintype "bidirectional"))
    )
    (net (code "68") (name "/GPIO53_FSIRXD1") (class "Default")
      (node (ref "U1") (pin "12") (pinfunction "GPIO53_12") (pintype "bidirectional"))
    )
    (net (code "69") (name "/GPIO54_FSIRXCLK") (class "Default")
      (node (ref "U1") (pin "13") (pinfunction "GPIO54_13") (pintype "bidirectional"))
    )
    (net (code "70") (name "/GPIO55") (class "Default")
      (node (ref "U1") (pin "43") (pinfunction "GPIO55_43") (pintype "bidirectional"))
    )
    (net (code "71") (name "/GPIO56") (class "Default")
      (node (ref "U1") (pin "65") (pinfunction "GPIO56_65") (pintype "bidirectional"))
    )
    (net (code "72") (name "/GPIO57") (class "Default")
      (node (ref "U1") (pin "66") (pinfunction "GPIO57_66") (pintype "bidirectional"))
    )
    (net (code "73") (name "/GPIO58") (class "Default")
      (node (ref "U1") (pin "67") (pinfunction "GPIO58_67") (pintype "bidirectional"))
    )
    (net (code "74") (name "/GPIO59") (class "Default")
      (node (ref "U1") (pin "92") (pinfunction "GPIO59_92") (pintype "bidirectional"))
    )
    (net (code "75") (name "/GPIO60") (class "Default")
      (node (ref "U1") (pin "44") (pinfunction "GPIO60_44") (pintype "bidirectional"))
    )
    (net (code "76") (name "/GPIO61") (class "Default")
      (node (ref "U1") (pin "91") (pinfunction "GPIO61_91") (pintype "bidirectional"))
    )
    (net (code "77") (name "/MCU_A0{slash}B15{slash}C15") (class "Default")
      (node (ref "C25") (pin "1") (pinfunction "1_1") (pintype "passive"))
      (node (ref "R12") (pin "2") (pinfunction "2_2") (pintype "passive"))
      (node (ref "U1") (pin "23") (pinfunction "A0/B15/C15/DACA_OUT_23") (pintype "passive"))
    )
    (net (code "78") (name "/MCU_A1{slash}B17") (class "Default")
      (node (ref "C33") (pin "1") (pinfunction "1_1") (pintype "passive"))
      (node (ref "R13") (pin "2") (pinfunction "2_2") (pintype "passive"))
      (node (ref "U1") (pin "22") (pinfunction "A1/B7/DACB_OUT_22") (pintype "passive"))
    )
    (net (code "79") (name "/MCU_A2{slash}B6{slash}C9") (class "Default")
      (node (ref "C26") (pin "1") (pinfunction "1_1") (pintype "passive"))
      (node (ref "R14") (pin "2") (pinfunction "2_2") (pintype "passive"))
      (node (ref "U1") (pin "17") (pinfunction "A2/B6/C9_17") (pintype "passive"))
    )
    (net (code "80") (name "/MCU_A3{slash}B9{slash}C7") (class "Default")
      (node (ref "C34") (pin "1") (pinfunction "1_1") (pintype "passive"))
      (node (ref "R15") (pin "2") (pinfunction "2_2") (pintype "passive"))
      (node (ref "U1") (pin "18") (pinfunction "A3/B9/C7_18") (pintype "passive"))
    )
    (net (code "81") (name "/MCU_A4{slash}B8") (class "Default")
      (node (ref "C27") (pin "1") (pinfunction "1_1") (pintype "passive"))
      (node (ref "R16") (pin "2") (pinfunction "2_2") (pintype "passive"))
      (node (ref "U1") (pin "36") (pinfunction "A4/B8_36") (pintype "passive"))
    )
    (net (code "82") (name "/MCU_A5") (class "Default")
      (node (ref "C35") (pin "1") (pinfunction "1_1") (pintype "passive"))
      (node (ref "R17") (pin "2") (pinfunction "2_2") (pintype "passive"))
      (node (ref "U1") (pin "35") (pinfunction "A5_35") (pintype "passive"))
    )
    (net (code "83") (name "/MCU_A6") (class "Default")
      (node (ref "C28") (pin "1") (pinfunction "1_1") (pintype "passive"))
      (node (ref "R18") (pin "2") (pinfunction "2_2") (pintype "passive"))
      (node (ref "U1") (pin "14") (pinfunction "A6_14") (pintype "passive"))
    )
    (net (code "84") (name "/MCU_A7{slash}C3") (class "Default")
      (node (ref "C36") (pin "1") (pinfunction "1_1") (pintype "passive"))
      (node (ref "R19") (pin "2") (pinfunction "2_2") (pintype "passive"))
      (node (ref "U1") (pin "31") (pinfunction "A7/C3_31") (pintype "passive"))
    )
    (net (code "85") (name "/MCU_A9") (class "Default")
      (node (ref "C29") (pin "1") (pinfunction "1_1") (pintype "passive"))
      (node (ref "R20") (pin "2") (pinfunction "2_2") (pintype "passive"))
      (node (ref "U1") (pin "38") (pinfunction "A9_38") (pintype "passive"))
    )
    (net (code "86") (name "/MCU_A10{slash}B1{slash}C10") (class "Default")
      (node (ref "C37") (pin "1") (pinfunction "1_1") (pintype "passive"))
      (node (ref "R21") (pin "2") (pinfunction "2_2") (pintype "passive"))
      (node (ref "U1") (pin "40") (pinfunction "A10/B1/C10_40") (pintype "passive"))
    )
    (net (code "87") (name "/MCU_A11{slash}B10{slash}C0") (class "Default")
      (node (ref "C30") (pin "1") (pinfunction "1_1") (pintype "passive"))
      (node (ref "R22") (pin "2") (pinfunction "2_2") (pintype "passive"))
      (node (ref "U1") (pin "20") (pinfunction "A11/B10/C0_20") (pintype "passive"))
    )
    (net (code "88") (name "/MCU_A12{slash}C5") (class "Default")
      (node (ref "C38") (pin "1") (pinfunction "1_1") (pintype "passive"))
      (node (ref "R23") (pin "2") (pinfunction "2_2") (pintype "passive"))
      (node (ref "U1") (pin "28") (pinfunction "A12/C5_28") (pintype "passive"))
    )
    (net (code "89") (name "/MCU_A14{slash}B14{slash}C4") (class "Default")
      (node (ref "C31") (pin "1") (pinfunction "1_1") (pintype "passive"))
      (node (ref "R24") (pin "2") (pinfunction "2_2") (pintype "passive"))
      (node (ref "U1") (pin "19") (pinfunction "A14/B14/C4_19") (pintype "passive"))
    )
    (net (code "90") (name "/MCU_B2{slash}C6") (class "Default")
      (node (ref "C39") (pin "1") (pinfunction "1_1") (pintype "passive"))
      (node (ref "R25") (pin "2") (pinfunction "2_2") (pintype "passive"))
      (node (ref "U1") (pin "15") (pinfunction "B2/C6_15") (pintype "passive"))
    )
    (net (code "91") (name "/MCU_B3") (class "Default")
      (node (ref "C32") (pin "1") (pinfunction "1_1") (pintype "passive"))
      (node (ref "R26") (pin "2") (pinfunction "2_2") (pintype "passive"))
      (node (ref "U1") (pin "16") (pinfunction "B3/VDAC_16") (pintype "passive"))
    )
    (net (code "92") (name "/MCU_B4{slash}C8") (class "Default")
      (node (ref "C40") (pin "1") (pinfunction "1_1") (pintype "passive"))
      (node (ref "R27") (pin "2") (pinfunction "2_2") (pintype "passive"))
      (node (ref "U1") (pin "39") (pinfunction "B4/C8_39") (pintype "passive"))
    )
    (net (code "93") (name "/MCU_B5") (class "Default")
      (node (ref "C75") (pin "1") (pinfunction "1_1") (pintype "passive"))
      (node (ref "R84") (pin "2") (pinfunction "2_2") (pintype "passive"))
      (node (ref "U1") (pin "32") (pinfunction "B5_32") (pintype "passive"))
    )
    (net (code "94") (name "/MCU_B11") (class "Default")
      (node (ref "C77") (pin "1") (pinfunction "1_1") (pintype "passive"))
      (node (ref "R85") (pin "2") (pinfunction "2_2") (pintype "passive"))
      (node (ref "U1") (pin "30") (pinfunction "B11_30") (pintype "passive"))
    )
    (net (code "95") (name "/MCU_B12{slash}C2") (class "Default")
      (node (ref "C76") (pin "1") (pinfunction "1_1") (pintype "passive"))
      (node (ref "R86") (pin "2") (pinfunction "2_2") (pintype "passive"))
      (node (ref "U1") (pin "21") (pinfunction "B12/C2_21") (pintype "passive"))
    )
    (net (code "96") (name "/MCU_C1") (class "Default")
      (node (ref "C78") (pin "1") (pinfunction "1_1") (pintype "passive"))
      (node (ref "R87") (pin "2") (pinfunction "2_2") (pintype "passive"))
      (node (ref "U1") (pin "29") (pinfunction "C1_29") (pintype "passive"))
    )
    (net (code "97") (name "/MCU_TCK") (class "Default")
      (node (ref "U1") (pin "60") (pinfunction "TCK_60") (pintype "input"))
    )
    (net (code "98") (name "/MCU_TDI") (class "Default")
      (node (ref "R44") (pin "2") (pinfunction "2_2") (pintype "passive"))
    )
    (net (code "99") (name "/MCU_TDO") (class "Default")
      (node (ref "R45") (pin "2") (pinfunction "2_2") (pintype "passive"))
    )
    (net (code "100") (name "/MCU_TMS") (class "Default")
      (node (ref "R10") (pin "1") (pinfunction "1_1") (pintype "passive"))
      (node (ref "U1") (pin "62") (pinfunction "TMS_62") (pintype "bidirectional"))
    )
    (net (code "101") (name "/VREFHI") (class "Default")
      (node (ref "C24") (pin "1") (pinfunction "1_1") (pintype "passive"))
      (node (ref "J15") (pin "1") (pinfunction "1_1") (pintype "passive"))
      (node (ref "U1") (pin "24") (pinfunction "VREFHIABC_24") (pintype "passive"))
      (node (ref "U1") (pin "25") (pinfunction "VREFHIABC_25") (pintype "passive"))
    )
    (net (code "102") (name "/XRSn") (class "Default")
      (node (ref "C17") (pin "2") (pinfunction "2_2") (pintype "passive"))
      (node (ref "R11") (pin "1") (pinfunction "1_1") (pintype "passive"))
      (node (ref "S1") (pin "4") (pinfunction "4_4") (pintype "passive"))
      (node (ref "U1") (pin "2") (pinfunction "~{XRS}_2") (pintype "open_collector"))
    )
    (net (code "103") (name "GND") (class "Default")
      (node (ref "C10") (pin "1") (pinfunction "1_1") (pintype "passive"))
      (node (ref "C11") (pin "1") (pinfunction "1_1") (pintype "passive"))
      (node (ref "C12") (pin "1") (pinfunction "1_1") (pintype "passive"))
      (node (ref "C13") (pin "1") (pinfunction "1_1") (pintype "passive"))
      (node (ref "C14") (pin "1") (pinfunction "1_1") (pintype "passive"))
      (node (ref "C15") (pin "2") (pinfunction "2_2") (pintype "passive"))
      (node (ref "C16") (pin "2") (pinfunction "2_2") (pintype "passive"))
      (node (ref "C17") (pin "1") (pinfunction "1_1") (pintype "passive"))
      (node (ref "C18") (pin "1") (pinfunction "1_1") (pintype "passive"))
      (node (ref "C19") (pin "1") (pinfunction "1_1") (pintype "passive"))
      (node (ref "C20") (pin "1") (pinfunction "1_1") (pintype "passive"))
      (node (ref "C21") (pin "1") (pinfunction "1_1") (pintype "passive"))
      (node (ref "C22") (pin "1") (pinfunction "1_1") (pintype "passive"))
      (node (ref "C23") (pin "1") (pinfunction "1_1") (pintype "passive"))
      (node (ref "C24") (pin "2") (pinfunction "2_2") (pintype "passive"))
      (node (ref "C25") (pin "2") (pinfunction "2_2") (pintype "passive"))
      (node (ref "C26") (pin "2") (pinfunction "2_2") (pintype "passive"))
      (node (ref "C27") (pin "2") (pinfunction "2_2") (pintype "passive"))
      (node (ref "C28") (pin "2") (pinfunction "2_2") (pintype "passive"))
      (node (ref "C29") (pin "2") (pinfunction "2_2") (pintype "passive"))
      (node (ref "C30") (pin "2") (pinfunction "2_2") (pintype "passive"))
      (node (ref "C31") (pin "2") (pinfunction "2_2") (pintype "passive"))
      (node (ref "C32") (pin "2") (pinfunction "2_2") (pintype "passive"))
      (node (ref "C33") (pin "2") (pinfunction "2_2") (pintype "passive"))
      (node (ref "C34") (pin "2") (pinfunction "2_2") (pintype "passive"))
      (node (ref "C35") (pin "2") (pinfunction "2_2") (pintype "passive"))
      (node (ref "C36") (pin "2") (pinfunction "2_2") (pintype "passive"))
      (node (ref "C37") (pin "2") (pinfunction "2_2") (pintype "passive"))
      (node (ref "C38") (pin "2") (pinfunction "2_2") (pintype "passive"))
      (node (ref "C39") (pin "2") (pinfunction "2_2") (pintype "passive"))
      (node (ref "C40") (pin "2") (pinfunction "2_2") (pintype "passive"))
      (node (ref "C75") (pin "2") (pinfunction "2_2") (pintype "passive"))
      (node (ref "C76") (pin "2") (pinfunction "2_2") (pintype "passive"))
      (node (ref "C77") (pin "2") (pinfunction "2_2") (pintype "passive"))
      (node (ref "C78") (pin "2") (pinfunction "2_2") (pintype "passive"))
      (node (ref "C9") (pin "1") (pinfunction "1_1") (pintype "passive"))
      (node (ref "J15") (pin "2") (pinfunction "2_2") (pintype "passive"))
      (node (ref "R83") (pin "2") (pinfunction "2_2") (pintype "passive"))
      (node (ref "S1") (pin "1") (pinfunction "1_1") (pintype "passive"))
      (node (ref "S1") (pin "2") (pinfunction "2_2") (pintype "passive"))
      (node (ref "S1") (pin "3") (pinfunction "3_3") (pintype "passive"))
      (node (ref "U1") (pin "26") (pinfunction "VREFLOABC_26") (pintype "passive"))
      (node (ref "U1") (pin "27") (pinfunction "VREFLOABC_27") (pintype "passive"))
      (node (ref "U1") (pin "33") (pinfunction "VSSA_33") (pintype "power_in"))
      (node (ref "U1") (pin "45") (pinfunction "VSS_45") (pintype "power_in"))
      (node (ref "U1") (pin "5") (pinfunction "VSS_5") (pintype "power_in"))
      (node (ref "U1") (pin "72") (pinfunction "VSS_72") (pintype "power_in"))
      (node (ref "U1") (pin "86") (pinfunction "VSS_86") (pintype "power_in"))
    )
    (net (code "104") (name "Net-(U1D-~{VREGEN})") (class "Default")
      (node (ref "R82") (pin "2") (pinfunction "2_2") (pintype "passive"))
      (node (ref "R83") (pin "1") (pinfunction "1_1") (pintype "passive"))
      (node (ref "U1") (pin "73") (pinfunction "~{VREGEN}_73") (pintype "input"))
    )
    (net (code "105") (name "VDD") (class "Default")
      (node (ref "C10") (pin "2") (pinfunction "2_2") (pintype "passive"))
      (node (ref "C11") (pin "2") (pinfunction "2_2") (pintype "passive"))
      (node (ref "C12") (pin "2") (pinfunction "2_2") (pintype "passive"))
      (node (ref "C13") (pin "2") (pinfunction "2_2") (pintype "passive"))
      (node (ref "C9") (pin "2") (pinfunction "2_2") (pintype "passive"))
      (node (ref "U1") (pin "4") (pinfunction "VDD_4") (pintype "power_in"))
      (node (ref "U1") (pin "46") (pinfunction "VDD_46") (pintype "power_in"))
      (node (ref "U1") (pin "71") (pinfunction "VDD_71") (pintype "power_in"))
      (node (ref "U1") (pin "87") (pinfunction "VDD_87") (pintype "power_in"))
    )
    (net (code "106") (name "VDDA") (class "Default")
      (node (ref "C14") (pin "2") (pinfunction "2_2") (pintype "passive"))
      (node (ref "C15") (pin "1") (pinfunction "1_1") (pintype "passive"))
      (node (ref "L2") (pin "2") (pinfunction "2_2") (pintype "passive"))
      (node (ref "U1") (pin "34") (pinfunction "VDDA_34") (pintype "power_in"))
    )
    (net (code "107") (name "VDDIO") (class "Default")
      (node (ref "C19") (pin "2") (pinfunction "2_2") (pintype "passive"))
      (node (ref "C20") (pin "2") (pinfunction "2_2") (pintype "passive"))
      (node (ref "C21") (pin "2") (pinfunction "2_2") (pintype "passive"))
      (node (ref "C22") (pin "2") (pinfunction "2_2") (pintype "passive"))
      (node (ref "C23") (pin "2") (pinfunction "2_2") (pintype "passive"))
      (node (ref "L3") (pin "2") (pinfunction "2_2") (pintype "passive"))
      (node (ref "U1") (pin "3") (pinfunction "VDDIO_3") (pintype "power_in"))
      (node (ref "U1") (pin "47") (pinfunction "VDDIO_47") (pintype "power_in"))
      (node (ref "U1") (pin "70") (pinfunction "VDDIO_70") (pintype "power_in"))
      (node (ref "U1") (pin "88") (pinfunction "VDDIO_88") (pintype "power_in"))
    )
    (net (code "108") (name "unconnected-(U1A-A8-Pad37)") (class "Default")
      (node (ref "U1") (pin "37") (pinfunction "A8_37") (pintype "passive+no_connect"))
    )
    (net (code "109") (name "unconnected-(U1A-B0{slash}C11-Pad41)") (class "Default")
      (node (ref "U1") (pin "41") (pinfunction "B0/C11_41") (pintype "passive+no_connect"))
    )
    (net (code "110") (name "unconnected-(U1A-C14-Pad42)") (class "Default")
      (node (ref "U1") (pin "42") (pinfunction "C14_42") (pintype "passive+no_connect"))
    )
  )
)
